# key20-ble.net
KiCad netlist of a schematic drawn in EAGLE
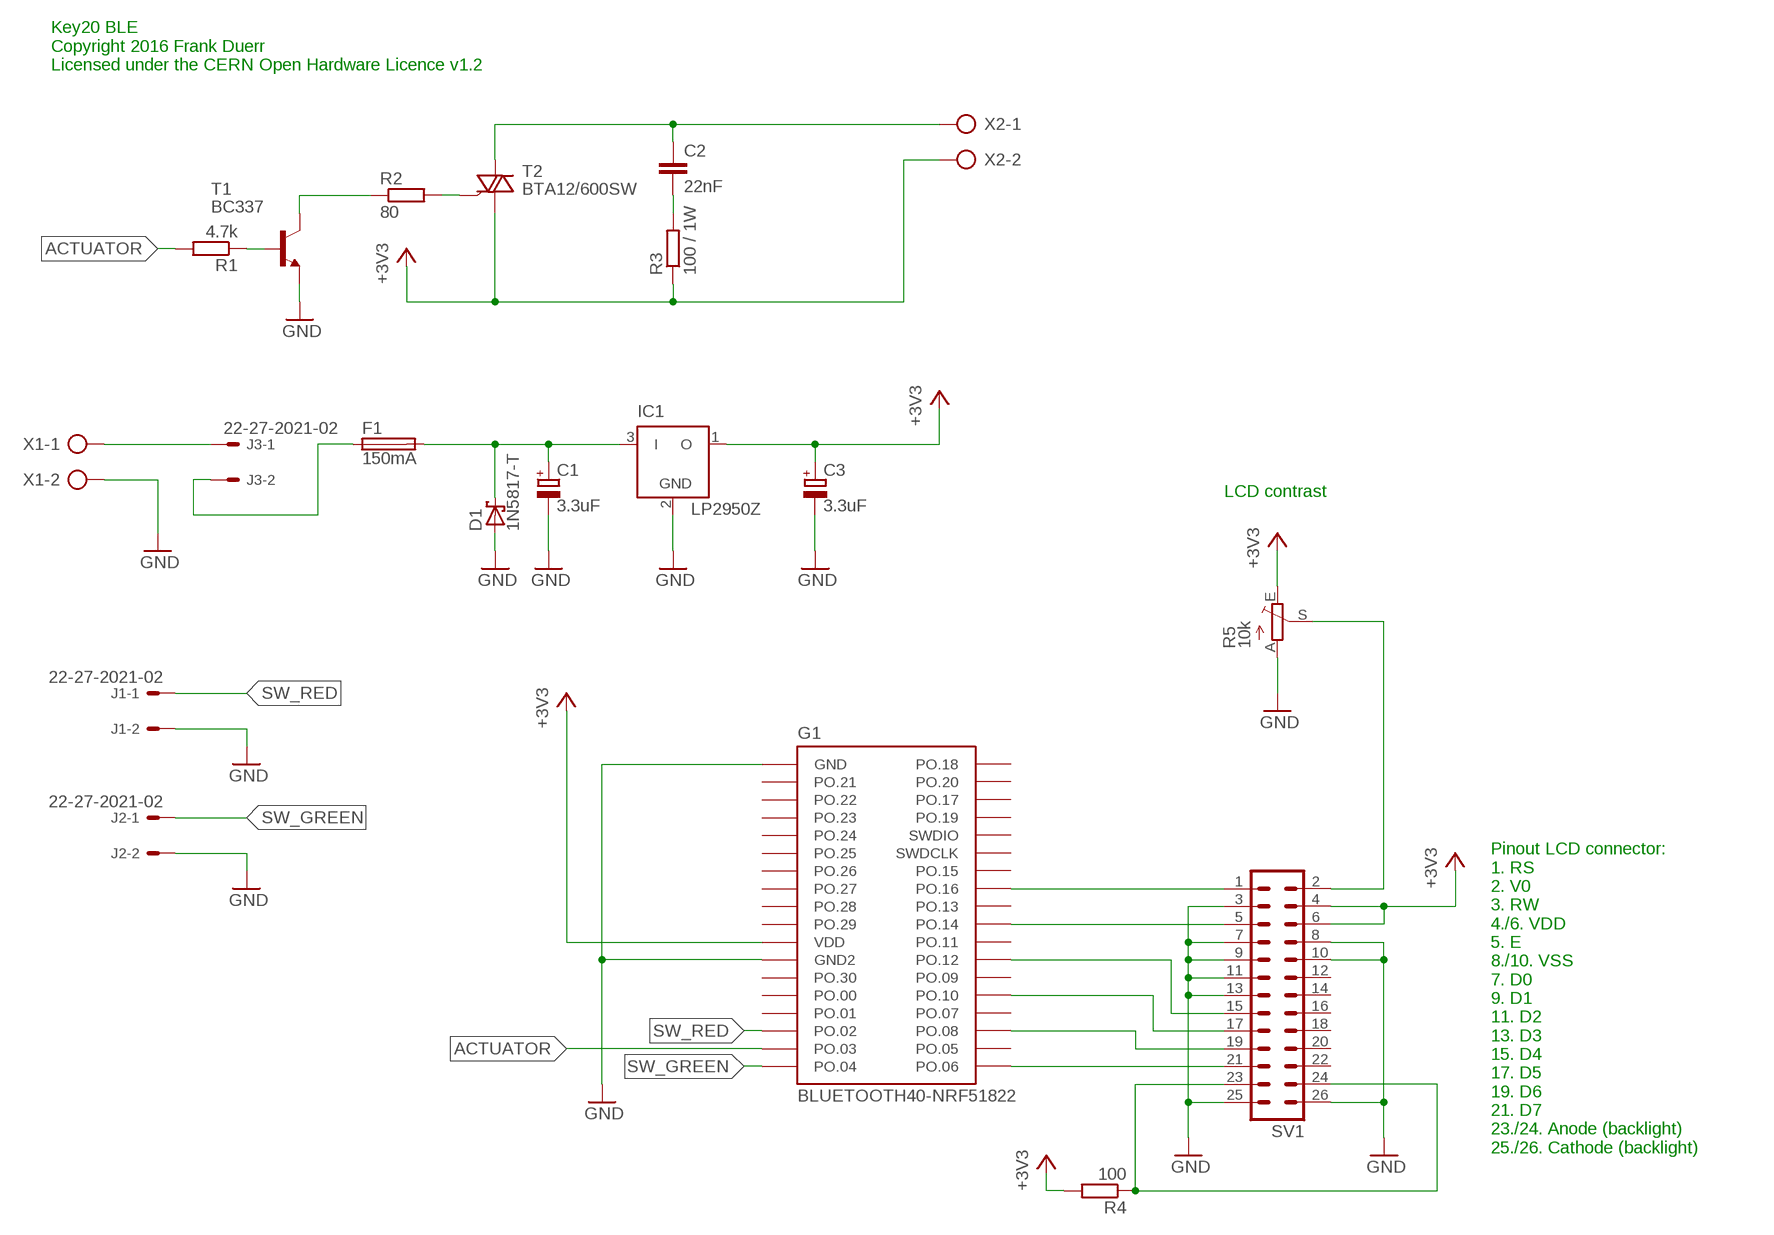
[diagram p0: schematic, sheet 1]

(export (version "E")
  (design (tool "Eeschema 10.0.6"))
  (components
    (comp (ref "C1")
      (value "3.3uF")
      (footprint "eagle-import:E2,5-5")
      (libsource (lib "eagle-import") (part "CPOL-EUE2.5-5"))
    )
    (comp (ref "C2")
      (value "22nF")
      (footprint "eagle-import:C102-054X133")
      (libsource (lib "eagle-import") (part "C-EU102-054X133"))
    )
    (comp (ref "C3")
      (value "3.3uF")
      (footprint "eagle-import:E2,5-5")
      (libsource (lib "eagle-import") (part "CPOL-EUE2.5-5"))
    )
    (comp (ref "D1")
      (value "1N5817-T")
      (footprint "eagle-import:DO41-7.6")
      (libsource (lib "eagle-import") (part "1N5817-T"))
    )
    (comp (ref "F1")
      (value "150mA")
      (footprint "eagle-import:SH22,5")
      (libsource (lib "eagle-import") (part "FUSESH22,5"))
    )
    (comp (ref "G1")
      (value "BLUETOOTH40-NRF51822")
      (footprint "eagle-import:BLUETOOTH40-NR51822")
      (libsource (lib "eagle-import") (part "BLUETOOTH40-NRF51822"))
    )
    (comp (ref "IC1")
      (value "LP2950Z")
      (footprint "eagle-import:TO92")
      (libsource (lib "eagle-import") (part "LP2950Z"))
    )
    (comp (ref "J1")
      (value "22-27-2021-02")
      (footprint "eagle-import:6410-02")
      (libsource (lib "eagle-import") (part "22-?-0227-2021"))
    )
    (comp (ref "J2")
      (value "22-27-2021-02")
      (footprint "eagle-import:6410-02")
      (libsource (lib "eagle-import") (part "22-?-0227-2021"))
    )
    (comp (ref "J3")
      (value "22-27-2021-02")
      (footprint "eagle-import:6410-02")
      (libsource (lib "eagle-import") (part "22-?-0227-2021"))
    )
    (comp (ref "R1")
      (value "4.7k")
      (footprint "eagle-import:0207_7")
      (libsource (lib "eagle-import") (part "R-EU_0207/7"))
    )
    (comp (ref "R2")
      (value "80")
      (footprint "eagle-import:0207_7")
      (libsource (lib "eagle-import") (part "R-EU_0207/7"))
    )
    (comp (ref "R3")
      (value "100 / 1W")
      (footprint "eagle-import:0207_7")
      (libsource (lib "eagle-import") (part "R-EU_0207/7"))
    )
    (comp (ref "R4")
      (value "100")
      (footprint "eagle-import:0207_7")
      (libsource (lib "eagle-import") (part "R-EU_0207/7"))
    )
    (comp (ref "R5")
      (value "10k")
      (footprint "eagle-import:CA6V")
      (libsource (lib "eagle-import") (part "TRIM_EU-CA6V"))
    )
    (comp (ref "SV1")
      (value "ML26")
      (footprint "eagle-import:ML26")
      (libsource (lib "eagle-import") (part "ML26"))
    )
    (comp (ref "T1")
      (value "BC337")
      (footprint "eagle-import:TO92")
      (libsource (lib "eagle-import") (part "BC337"))
    )
    (comp (ref "T2")
      (value "BTA12/600SW")
      (footprint "eagle-import:TO220BV")
      (libsource (lib "eagle-import") (part "TIC206M"))
    )
    (comp (ref "X1")
      (value "AK500/2")
      (footprint "eagle-import:AK500_2")
      (libsource (lib "eagle-import") (part "AK500/2"))
    )
    (comp (ref "X2")
      (value "AK500/2")
      (footprint "eagle-import:AK500_2")
      (libsource (lib "eagle-import") (part "AK500/2"))
    )
  )
  (nets
    (net (code "1") (name "+3V3") (class "Default")
      (node (ref "C3") (pin "+") (pinfunction "+_+") (pintype "passive"))
      (node (ref "G1") (pin "VDD") (pinfunction "VDD_VDD") (pintype "power_in"))
      (node (ref "IC1") (pin "1") (pinfunction "O_1") (pintype "input"))
      (node (ref "R3") (pin "1") (pinfunction "1_1") (pintype "passive"))
      (node (ref "R4") (pin "2") (pinfunction "2_2") (pintype "passive"))
      (node (ref "R5") (pin "E") (pinfunction "E_E") (pintype "passive"))
      (node (ref "SV1") (pin "4") (pinfunction "4_4") (pintype "passive"))
      (node (ref "SV1") (pin "6") (pinfunction "6_6") (pintype "passive"))
      (node (ref "T2") (pin "T1") (pinfunction "A1_T1") (pintype "passive"))
      (node (ref "X2") (pin "2") (pinfunction "KL_2") (pintype "passive"))
    )
    (net (code "2") (name "ACTUATOR") (class "Default")
      (node (ref "G1") (pin "PO.03") (pinfunction "PO.03_PO.03") (pintype "bidirectional"))
      (node (ref "R1") (pin "2") (pinfunction "2_2") (pintype "passive"))
    )
    (net (code "3") (name "GND") (class "Default")
      (node (ref "C1") (pin "-") (pinfunction "-_-") (pintype "passive"))
      (node (ref "C3") (pin "-") (pinfunction "-_-") (pintype "passive"))
      (node (ref "D1") (pin "A") (pinfunction "A_A") (pintype "passive"))
      (node (ref "G1") (pin "GND") (pinfunction "GND_GND") (pintype "power_in"))
      (node (ref "G1") (pin "GND2") (pinfunction "GND2_GND2") (pintype "power_in"))
      (node (ref "IC1") (pin "2") (pinfunction "GND_2") (pintype "power_in"))
      (node (ref "J1") (pin "2") (pinfunction "S_2") (pintype "passive"))
      (node (ref "J2") (pin "2") (pinfunction "S_2") (pintype "passive"))
      (node (ref "R5") (pin "A") (pinfunction "A_A") (pintype "passive"))
      (node (ref "SV1") (pin "10") (pinfunction "10_10") (pintype "passive"))
      (node (ref "SV1") (pin "11") (pinfunction "11_11") (pintype "passive"))
      (node (ref "SV1") (pin "13") (pinfunction "13_13") (pintype "passive"))
      (node (ref "SV1") (pin "25") (pinfunction "25_25") (pintype "passive"))
      (node (ref "SV1") (pin "26") (pinfunction "26_26") (pintype "passive"))
      (node (ref "SV1") (pin "3") (pinfunction "3_3") (pintype "passive"))
      (node (ref "SV1") (pin "7") (pinfunction "7_7") (pintype "passive"))
      (node (ref "SV1") (pin "8") (pinfunction "8_8") (pintype "passive"))
      (node (ref "SV1") (pin "9") (pinfunction "9_9") (pintype "passive"))
      (node (ref "T1") (pin "1") (pinfunction "E_1") (pintype "passive"))
      (node (ref "X1") (pin "2") (pinfunction "KL_2") (pintype "passive"))
    )
    (net (code "4") (name "Net-(C2-Pad2)") (class "Default")
      (node (ref "C2") (pin "2") (pinfunction "2_2") (pintype "passive"))
      (node (ref "R3") (pin "2") (pinfunction "2_2") (pintype "passive"))
    )
    (net (code "5") (name "Net-(G1-PadPO.06)") (class "Default")
      (node (ref "G1") (pin "PO.06") (pinfunction "PO.06_PO.06") (pintype "bidirectional"))
      (node (ref "SV1") (pin "21") (pinfunction "21_21") (pintype "passive"))
    )
    (net (code "6") (name "Net-(G1-PadPO.08)") (class "Default")
      (node (ref "G1") (pin "PO.08") (pinfunction "PO.08_PO.08") (pintype "bidirectional"))
      (node (ref "SV1") (pin "19") (pinfunction "19_19") (pintype "passive"))
    )
    (net (code "7") (name "Net-(G1-PadPO.10)") (class "Default")
      (node (ref "G1") (pin "PO.10") (pinfunction "PO.10_PO.10") (pintype "bidirectional"))
      (node (ref "SV1") (pin "17") (pinfunction "17_17") (pintype "passive"))
    )
    (net (code "8") (name "Net-(G1-PadPO.12)") (class "Default")
      (node (ref "G1") (pin "PO.12") (pinfunction "PO.12_PO.12") (pintype "bidirectional"))
      (node (ref "SV1") (pin "15") (pinfunction "15_15") (pintype "passive"))
    )
    (net (code "9") (name "Net-(G1-PadPO.14)") (class "Default")
      (node (ref "G1") (pin "PO.14") (pinfunction "PO.14_PO.14") (pintype "bidirectional"))
      (node (ref "SV1") (pin "5") (pinfunction "5_5") (pintype "passive"))
    )
    (net (code "10") (name "Net-(G1-PadPO.16)") (class "Default")
      (node (ref "G1") (pin "PO.16") (pinfunction "PO.16_PO.16") (pintype "bidirectional"))
      (node (ref "SV1") (pin "1") (pinfunction "1_1") (pintype "passive"))
    )
    (net (code "11") (name "Net-(IC1-I)") (class "Default")
      (node (ref "C1") (pin "+") (pinfunction "+_+") (pintype "passive"))
      (node (ref "D1") (pin "C") (pinfunction "C_C") (pintype "passive"))
      (node (ref "F1") (pin "2") (pinfunction "2_2") (pintype "passive"))
      (node (ref "IC1") (pin "3") (pinfunction "I_3") (pintype "input"))
    )
    (net (code "12") (name "Net-(J3A-S)") (class "Default")
      (node (ref "J3") (pin "1") (pinfunction "S_1") (pintype "passive"))
      (node (ref "X1") (pin "1") (pinfunction "KL_1") (pintype "passive"))
    )
    (net (code "13") (name "Net-(J3B-S)") (class "Default")
      (node (ref "F1") (pin "1") (pinfunction "1_1") (pintype "passive"))
      (node (ref "J3") (pin "2") (pinfunction "S_2") (pintype "passive"))
    )
    (net (code "14") (name "Net-(R2-Pad2)") (class "Default")
      (node (ref "R2") (pin "2") (pinfunction "2_2") (pintype "passive"))
      (node (ref "T2") (pin "G") (pinfunction "G_G") (pintype "passive"))
    )
    (net (code "15") (name "Net-(R4-Pad1)") (class "Default")
      (node (ref "R4") (pin "1") (pinfunction "1_1") (pintype "passive"))
      (node (ref "SV1") (pin "23") (pinfunction "23_23") (pintype "passive"))
      (node (ref "SV1") (pin "24") (pinfunction "24_24") (pintype "passive"))
    )
    (net (code "16") (name "Net-(R5-PadS)") (class "Default")
      (node (ref "R5") (pin "S") (pinfunction "S_S") (pintype "passive"))
      (node (ref "SV1") (pin "2") (pinfunction "2_2") (pintype "passive"))
    )
    (net (code "17") (name "Net-(T1-B)") (class "Default")
      (node (ref "R1") (pin "1") (pinfunction "1_1") (pintype "passive"))
      (node (ref "T1") (pin "2") (pinfunction "B_2") (pintype "passive"))
    )
    (net (code "18") (name "Net-(T1-C)") (class "Default")
      (node (ref "R2") (pin "1") (pinfunction "1_1") (pintype "passive"))
      (node (ref "T1") (pin "3") (pinfunction "C_3") (pintype "passive"))
    )
    (net (code "19") (name "Net-(T2-A2)") (class "Default")
      (node (ref "C2") (pin "1") (pinfunction "1_1") (pintype "passive"))
      (node (ref "T2") (pin "T2") (pinfunction "A2_T2") (pintype "passive"))
      (node (ref "X2") (pin "1") (pinfunction "KL_1") (pintype "passive"))
    )
    (net (code "20") (name "SW_GREEN") (class "Default")
      (node (ref "G1") (pin "PO.04") (pinfunction "PO.04_PO.04") (pintype "bidirectional"))
      (node (ref "J2") (pin "1") (pinfunction "S_1") (pintype "passive"))
    )
    (net (code "21") (name "SW_RED") (class "Default")
      (node (ref "G1") (pin "PO.02") (pinfunction "PO.02_PO.02") (pintype "bidirectional"))
      (node (ref "J1") (pin "1") (pinfunction "S_1") (pintype "passive"))
    )
    (net (code "22") (name "unconnected-(G1-PadPO.00)") (class "Default")
      (node (ref "G1") (pin "PO.00") (pinfunction "PO.00_PO.00") (pintype "bidirectional"))
    )
    (net (code "23") (name "unconnected-(G1-PadPO.01)") (class "Default")
      (node (ref "G1") (pin "PO.01") (pinfunction "PO.01_PO.01") (pintype "bidirectional"))
    )
    (net (code "24") (name "unconnected-(G1-PadPO.05)") (class "Default")
      (node (ref "G1") (pin "PO.05") (pinfunction "PO.05_PO.05") (pintype "bidirectional"))
    )
    (net (code "25") (name "unconnected-(G1-PadPO.07)") (class "Default")
      (node (ref "G1") (pin "PO.07") (pinfunction "PO.07_PO.07") (pintype "bidirectional"))
    )
    (net (code "26") (name "unconnected-(G1-PadPO.09)") (class "Default")
      (node (ref "G1") (pin "PO.09") (pinfunction "PO.09_PO.09") (pintype "bidirectional"))
    )
    (net (code "27") (name "unconnected-(G1-PadPO.11)") (class "Default")
      (node (ref "G1") (pin "PO.11") (pinfunction "PO.11_PO.11") (pintype "bidirectional"))
    )
    (net (code "28") (name "unconnected-(G1-PadPO.13)") (class "Default")
      (node (ref "G1") (pin "PO.13") (pinfunction "PO.13_PO.13") (pintype "bidirectional"))
    )
    (net (code "29") (name "unconnected-(G1-PadPO.15)") (class "Default")
      (node (ref "G1") (pin "PO.15") (pinfunction "PO.15_PO.15") (pintype "bidirectional"))
    )
    (net (code "30") (name "unconnected-(G1-PadPO.17)") (class "Default")
      (node (ref "G1") (pin "PO.17") (pinfunction "PO.17_PO.17") (pintype "bidirectional"))
    )
    (net (code "31") (name "unconnected-(G1-PadPO.18)") (class "Default")
      (node (ref "G1") (pin "PO.18") (pinfunction "PO.18_PO.18") (pintype "bidirectional"))
    )
    (net (code "32") (name "unconnected-(G1-PadPO.19)") (class "Default")
      (node (ref "G1") (pin "PO.19") (pinfunction "PO.19_PO.19") (pintype "bidirectional"))
    )
    (net (code "33") (name "unconnected-(G1-PadPO.20)") (class "Default")
      (node (ref "G1") (pin "PO.20") (pinfunction "PO.20_PO.20") (pintype "bidirectional"))
    )
    (net (code "34") (name "unconnected-(G1-PadPO.21)") (class "Default")
      (node (ref "G1") (pin "PO.21") (pinfunction "PO.21_PO.21") (pintype "bidirectional"))
    )
    (net (code "35") (name "unconnected-(G1-PadPO.22)") (class "Default")
      (node (ref "G1") (pin "PO.22") (pinfunction "PO.22_PO.22") (pintype "bidirectional"))
    )
    (net (code "36") (name "unconnected-(G1-PadPO.23)") (class "Default")
      (node (ref "G1") (pin "PO.23") (pinfunction "PO.23_PO.23") (pintype "bidirectional"))
    )
    (net (code "37") (name "unconnected-(G1-PadPO.24)") (class "Default")
      (node (ref "G1") (pin "PO.24") (pinfunction "PO.24_PO.24") (pintype "bidirectional"))
    )
    (net (code "38") (name "unconnected-(G1-PadPO.25)") (class "Default")
      (node (ref "G1") (pin "PO.25") (pinfunction "PO.25_PO.25") (pintype "bidirectional"))
    )
    (net (code "39") (name "unconnected-(G1-PadPO.26)") (class "Default")
      (node (ref "G1") (pin "PO.26") (pinfunction "PO.26_PO.26") (pintype "bidirectional"))
    )
    (net (code "40") (name "unconnected-(G1-PadPO.27)") (class "Default")
      (node (ref "G1") (pin "PO.27") (pinfunction "PO.27_PO.27") (pintype "bidirectional"))
    )
    (net (code "41") (name "unconnected-(G1-PadPO.28)") (class "Default")
      (node (ref "G1") (pin "PO.28") (pinfunction "PO.28_PO.28") (pintype "bidirectional"))
    )
    (net (code "42") (name "unconnected-(G1-PadPO.29)") (class "Default")
      (node (ref "G1") (pin "PO.29") (pinfunction "PO.29_PO.29") (pintype "bidirectional"))
    )
    (net (code "43") (name "unconnected-(G1-PadPO.30)") (class "Default")
      (node (ref "G1") (pin "PO.30") (pinfunction "PO.30_PO.30") (pintype "bidirectional"))
    )
    (net (code "44") (name "unconnected-(G1-PadSWDCLK)") (class "Default")
      (node (ref "G1") (pin "SWDCLK") (pinfunction "SWDCLK_SWDCLK") (pintype "bidirectional"))
    )
    (net (code "45") (name "unconnected-(G1-PadSWDIO)") (class "Default")
      (node (ref "G1") (pin "SWDIO") (pinfunction "SWDIO_SWDIO") (pintype "bidirectional"))
    )
    (net (code "46") (name "unconnected-(SV1-Pad12)") (class "Default")
      (node (ref "SV1") (pin "12") (pinfunction "12_12") (pintype "passive"))
    )
    (net (code "47") (name "unconnected-(SV1-Pad14)") (class "Default")
      (node (ref "SV1") (pin "14") (pinfunction "14_14") (pintype "passive"))
    )
    (net (code "48") (name "unconnected-(SV1-Pad16)") (class "Default")
      (node (ref "SV1") (pin "16") (pinfunction "16_16") (pintype "passive"))
    )
    (net (code "49") (name "unconnected-(SV1-Pad18)") (class "Default")
      (node (ref "SV1") (pin "18") (pinfunction "18_18") (pintype "passive"))
    )
    (net (code "50") (name "unconnected-(SV1-Pad20)") (class "Default")
      (node (ref "SV1") (pin "20") (pinfunction "20_20") (pintype "passive"))
    )
    (net (code "51") (name "unconnected-(SV1-Pad22)") (class "Default")
      (node (ref "SV1") (pin "22") (pinfunction "22_22") (pintype "passive"))
    )
  )
)
